# Adafruit_Si5351A.net
KiCad netlist of a schematic drawn in EAGLE
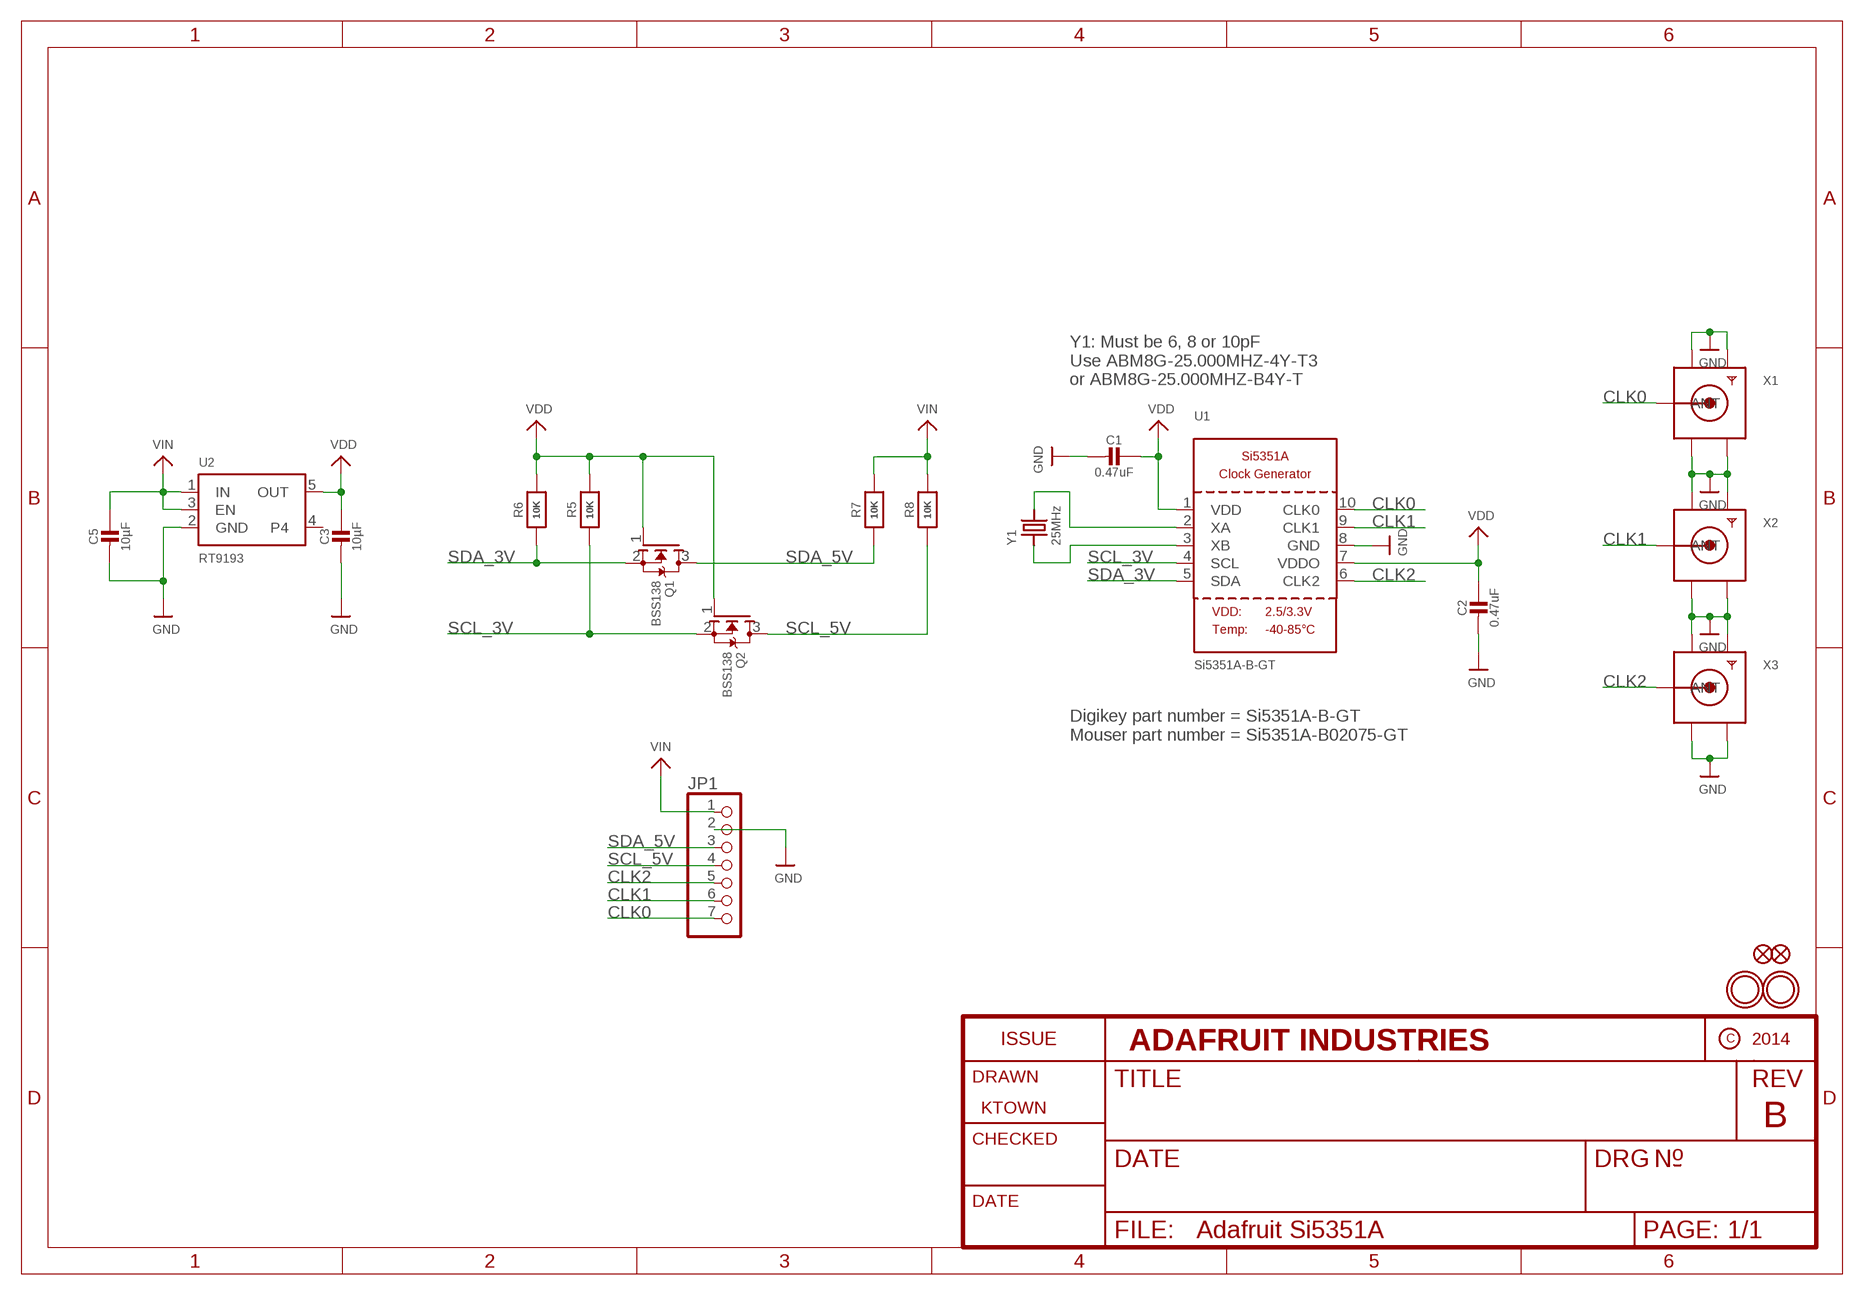
[diagram p0: schematic, sheet 1]

(export (version "E")
  (design (tool "Eeschema 10.0.6"))
  (components
    (comp (ref "C1")
      (value "0.47uF")
      (footprint "eagle-import:0805-NO")
      (libsource (lib "eagle-import") (part "CAP_CERAMIC0805-NOOUTLINE"))
    )
    (comp (ref "C2")
      (value "0.47uF")
      (footprint "eagle-import:0805-NO")
      (libsource (lib "eagle-import") (part "CAP_CERAMIC0805-NOOUTLINE"))
    )
    (comp (ref "C3")
      (value "10µF")
      (footprint "eagle-import:0805-NO")
      (libsource (lib "eagle-import") (part "CAP_CERAMIC0805-NOOUTLINE"))
    )
    (comp (ref "C5")
      (value "10µF")
      (footprint "eagle-import:0805-NO")
      (libsource (lib "eagle-import") (part "CAP_CERAMIC0805-NOOUTLINE"))
    )
    (comp (ref "FID1")
      (value "FIDUCIAL\"\"")
      (footprint "eagle-import:FIDUCIAL_1MM")
      (libsource (lib "eagle-import") (part "FIDUCIAL{dblquote}{dblquote}"))
    )
    (comp (ref "FID2")
      (value "FIDUCIAL\"\"")
      (footprint "eagle-import:FIDUCIAL_1MM")
      (libsource (lib "eagle-import") (part "FIDUCIAL{dblquote}{dblquote}"))
    )
    (comp (ref "JP1")
      (value "HEADER-1X7THICKER")
      (footprint "eagle-import:1X07_ROUND_76")
      (libsource (lib "eagle-import") (part "HEADER-1X7THICKER"))
    )
    (comp (ref "Q1")
      (value "BSS138")
      (footprint "eagle-import:SOT23-WIDE")
      (libsource (lib "eagle-import") (part "MOSFET-NWIDE"))
    )
    (comp (ref "Q2")
      (value "BSS138")
      (footprint "eagle-import:SOT23-WIDE")
      (libsource (lib "eagle-import") (part "MOSFET-NWIDE"))
    )
    (comp (ref "R5")
      (value "10K")
      (footprint "eagle-import:0805-NO")
      (libsource (lib "eagle-import") (part "RESISTOR0805_NOOUTLINE"))
    )
    (comp (ref "R6")
      (value "10K")
      (footprint "eagle-import:0805-NO")
      (libsource (lib "eagle-import") (part "RESISTOR0805_NOOUTLINE"))
    )
    (comp (ref "R7")
      (value "10K")
      (footprint "eagle-import:0805-NO")
      (libsource (lib "eagle-import") (part "RESISTOR0805_NOOUTLINE"))
    )
    (comp (ref "R8")
      (value "10K")
      (footprint "eagle-import:0805-NO")
      (libsource (lib "eagle-import") (part "RESISTOR0805_NOOUTLINE"))
    )
    (comp (ref "U$10")
      (value "MOUNTINGHOLE2.5")
      (footprint "eagle-import:MOUNTINGHOLE_2.5_PLATED")
      (libsource (lib "eagle-import") (part "MOUNTINGHOLE2.5"))
    )
    (comp (ref "U$11")
      (value "MOUNTINGHOLE2.5")
      (footprint "eagle-import:MOUNTINGHOLE_2.5_PLATED")
      (libsource (lib "eagle-import") (part "MOUNTINGHOLE2.5"))
    )
    (comp (ref "U1")
      (value "Si5351A-B-GT")
      (footprint "eagle-import:MSOP10")
      (libsource (lib "eagle-import") (part "SI5351A"))
    )
    (comp (ref "U2")
      (value "RT9193")
      (footprint "eagle-import:SOT23-5")
      (libsource (lib "eagle-import") (part "VREG_SOT23-5"))
    )
    (comp (ref "X1")
      (value "SMACONNECTOR_EDGE")
      (footprint "eagle-import:SMA_EDGELAUNCH")
      (libsource (lib "eagle-import") (part "SMACONNECTOR_EDGE"))
    )
    (comp (ref "X2")
      (value "SMACONNECTOR_EDGE")
      (footprint "eagle-import:SMA_EDGELAUNCH")
      (libsource (lib "eagle-import") (part "SMACONNECTOR_EDGE"))
    )
    (comp (ref "X3")
      (value "SMACONNECTOR_EDGE")
      (footprint "eagle-import:SMA_EDGELAUNCH")
      (libsource (lib "eagle-import") (part "SMACONNECTOR_EDGE"))
    )
    (comp (ref "Y1")
      (value "25MHz")
      (footprint "eagle-import:CRYSTAL_3.2X2.5")
      (libsource (lib "eagle-import") (part "CRYSTAL3.2X2.5"))
    )
  )
  (nets
    (net (code "1") (name "/CLK0") (class "Default")
      (node (ref "JP1") (pin "7") (pinfunction "7_7") (pintype "passive"))
      (node (ref "U1") (pin "10") (pinfunction "CLK0_10") (pintype "output"))
      (node (ref "X1") (pin "P") (pinfunction "ANT_P") (pintype "bidirectional"))
    )
    (net (code "2") (name "/CLK1") (class "Default")
      (node (ref "JP1") (pin "6") (pinfunction "6_6") (pintype "passive"))
      (node (ref "U1") (pin "9") (pinfunction "CLK1_9") (pintype "output"))
      (node (ref "X2") (pin "P") (pinfunction "ANT_P") (pintype "bidirectional"))
    )
    (net (code "3") (name "/CLK2") (class "Default")
      (node (ref "JP1") (pin "5") (pinfunction "5_5") (pintype "passive"))
      (node (ref "U1") (pin "6") (pinfunction "CLK2_6") (pintype "output"))
      (node (ref "X3") (pin "P") (pinfunction "ANT_P") (pintype "bidirectional"))
    )
    (net (code "4") (name "/SCL_3V") (class "Default")
      (node (ref "Q2") (pin "2") (pinfunction "S_2") (pintype "bidirectional"))
      (node (ref "R5") (pin "1") (pinfunction "1_1") (pintype "passive"))
      (node (ref "U1") (pin "4") (pinfunction "SCL_4") (pintype "input"))
    )
    (net (code "5") (name "/SCL_5V") (class "Default")
      (node (ref "JP1") (pin "4") (pinfunction "4_4") (pintype "passive"))
      (node (ref "Q2") (pin "3") (pinfunction "D_3") (pintype "bidirectional"))
      (node (ref "R8") (pin "1") (pinfunction "1_1") (pintype "passive"))
    )
    (net (code "6") (name "/SDA_3V") (class "Default")
      (node (ref "Q1") (pin "2") (pinfunction "S_2") (pintype "bidirectional"))
      (node (ref "R6") (pin "1") (pinfunction "1_1") (pintype "passive"))
      (node (ref "U1") (pin "5") (pinfunction "SDA_5") (pintype "bidirectional"))
    )
    (net (code "7") (name "/SDA_5V") (class "Default")
      (node (ref "JP1") (pin "3") (pinfunction "3_3") (pintype "passive"))
      (node (ref "Q1") (pin "3") (pinfunction "D_3") (pintype "bidirectional"))
      (node (ref "R7") (pin "1") (pinfunction "1_1") (pintype "passive"))
    )
    (net (code "8") (name "GND") (class "Default")
      (node (ref "C1") (pin "2") (pinfunction "2_2") (pintype "passive"))
      (node (ref "C2") (pin "2") (pinfunction "2_2") (pintype "passive"))
      (node (ref "C3") (pin "2") (pinfunction "2_2") (pintype "passive"))
      (node (ref "C5") (pin "2") (pinfunction "2_2") (pintype "passive"))
      (node (ref "JP1") (pin "2") (pinfunction "2_2") (pintype "passive"))
      (node (ref "U1") (pin "8") (pinfunction "GND_8") (pintype "power_in"))
      (node (ref "U2") (pin "2") (pinfunction "GND_2") (pintype "power_in"))
      (node (ref "X1") (pin "GND@1") (pinfunction "GND4_GND@1") (pintype "power_in"))
      (node (ref "X1") (pin "GND@2") (pinfunction "GND3_GND@2") (pintype "power_in"))
      (node (ref "X1") (pin "GND@3") (pinfunction "GND2_GND@3") (pintype "power_in"))
      (node (ref "X1") (pin "GND@4") (pinfunction "GND1_GND@4") (pintype "power_in"))
      (node (ref "X2") (pin "GND@1") (pinfunction "GND4_GND@1") (pintype "power_in"))
      (node (ref "X2") (pin "GND@2") (pinfunction "GND3_GND@2") (pintype "power_in"))
      (node (ref "X2") (pin "GND@3") (pinfunction "GND2_GND@3") (pintype "power_in"))
      (node (ref "X2") (pin "GND@4") (pinfunction "GND1_GND@4") (pintype "power_in"))
      (node (ref "X3") (pin "GND@1") (pinfunction "GND4_GND@1") (pintype "power_in"))
      (node (ref "X3") (pin "GND@2") (pinfunction "GND3_GND@2") (pintype "power_in"))
      (node (ref "X3") (pin "GND@3") (pinfunction "GND2_GND@3") (pintype "power_in"))
      (node (ref "X3") (pin "GND@4") (pinfunction "GND1_GND@4") (pintype "power_in"))
    )
    (net (code "9") (name "Net-(U1-XA)") (class "Default")
      (node (ref "U1") (pin "2") (pinfunction "XA_2") (pintype "input"))
      (node (ref "Y1") (pin "2") (pinfunction "2_2") (pintype "passive"))
    )
    (net (code "10") (name "Net-(U1-XB)") (class "Default")
      (node (ref "U1") (pin "3") (pinfunction "XB_3") (pintype "input"))
      (node (ref "Y1") (pin "1") (pinfunction "1_1") (pintype "passive"))
    )
    (net (code "11") (name "VDD") (class "Default")
      (node (ref "C1") (pin "1") (pinfunction "1_1") (pintype "passive"))
      (node (ref "C2") (pin "1") (pinfunction "1_1") (pintype "passive"))
      (node (ref "C3") (pin "1") (pinfunction "1_1") (pintype "passive"))
      (node (ref "Q1") (pin "1") (pinfunction "G_1") (pintype "bidirectional"))
      (node (ref "Q2") (pin "1") (pinfunction "G_1") (pintype "bidirectional"))
      (node (ref "R5") (pin "2") (pinfunction "2_2") (pintype "passive"))
      (node (ref "R6") (pin "2") (pinfunction "2_2") (pintype "passive"))
      (node (ref "U1") (pin "1") (pinfunction "VDD_1") (pintype "power_in"))
      (node (ref "U1") (pin "7") (pinfunction "VDDO_7") (pintype "power_in"))
      (node (ref "U2") (pin "5") (pinfunction "OUT_5") (pintype "power_in"))
    )
    (net (code "12") (name "VIN") (class "Default")
      (node (ref "C5") (pin "1") (pinfunction "1_1") (pintype "passive"))
      (node (ref "JP1") (pin "1") (pinfunction "1_1") (pintype "passive"))
      (node (ref "R7") (pin "2") (pinfunction "2_2") (pintype "passive"))
      (node (ref "R8") (pin "2") (pinfunction "2_2") (pintype "passive"))
      (node (ref "U2") (pin "1") (pinfunction "IN_1") (pintype "power_in"))
      (node (ref "U2") (pin "3") (pinfunction "EN_3") (pintype "input"))
    )
    (net (code "13") (name "unconnected-(U2-P4-Pad4)") (class "Default")
      (node (ref "U2") (pin "4") (pinfunction "P4_4") (pintype "bidirectional"))
    )
  )
)
